# Eurorack_current_measure_PCB.net
KiCad netlist of a schematic drawn in EAGLE
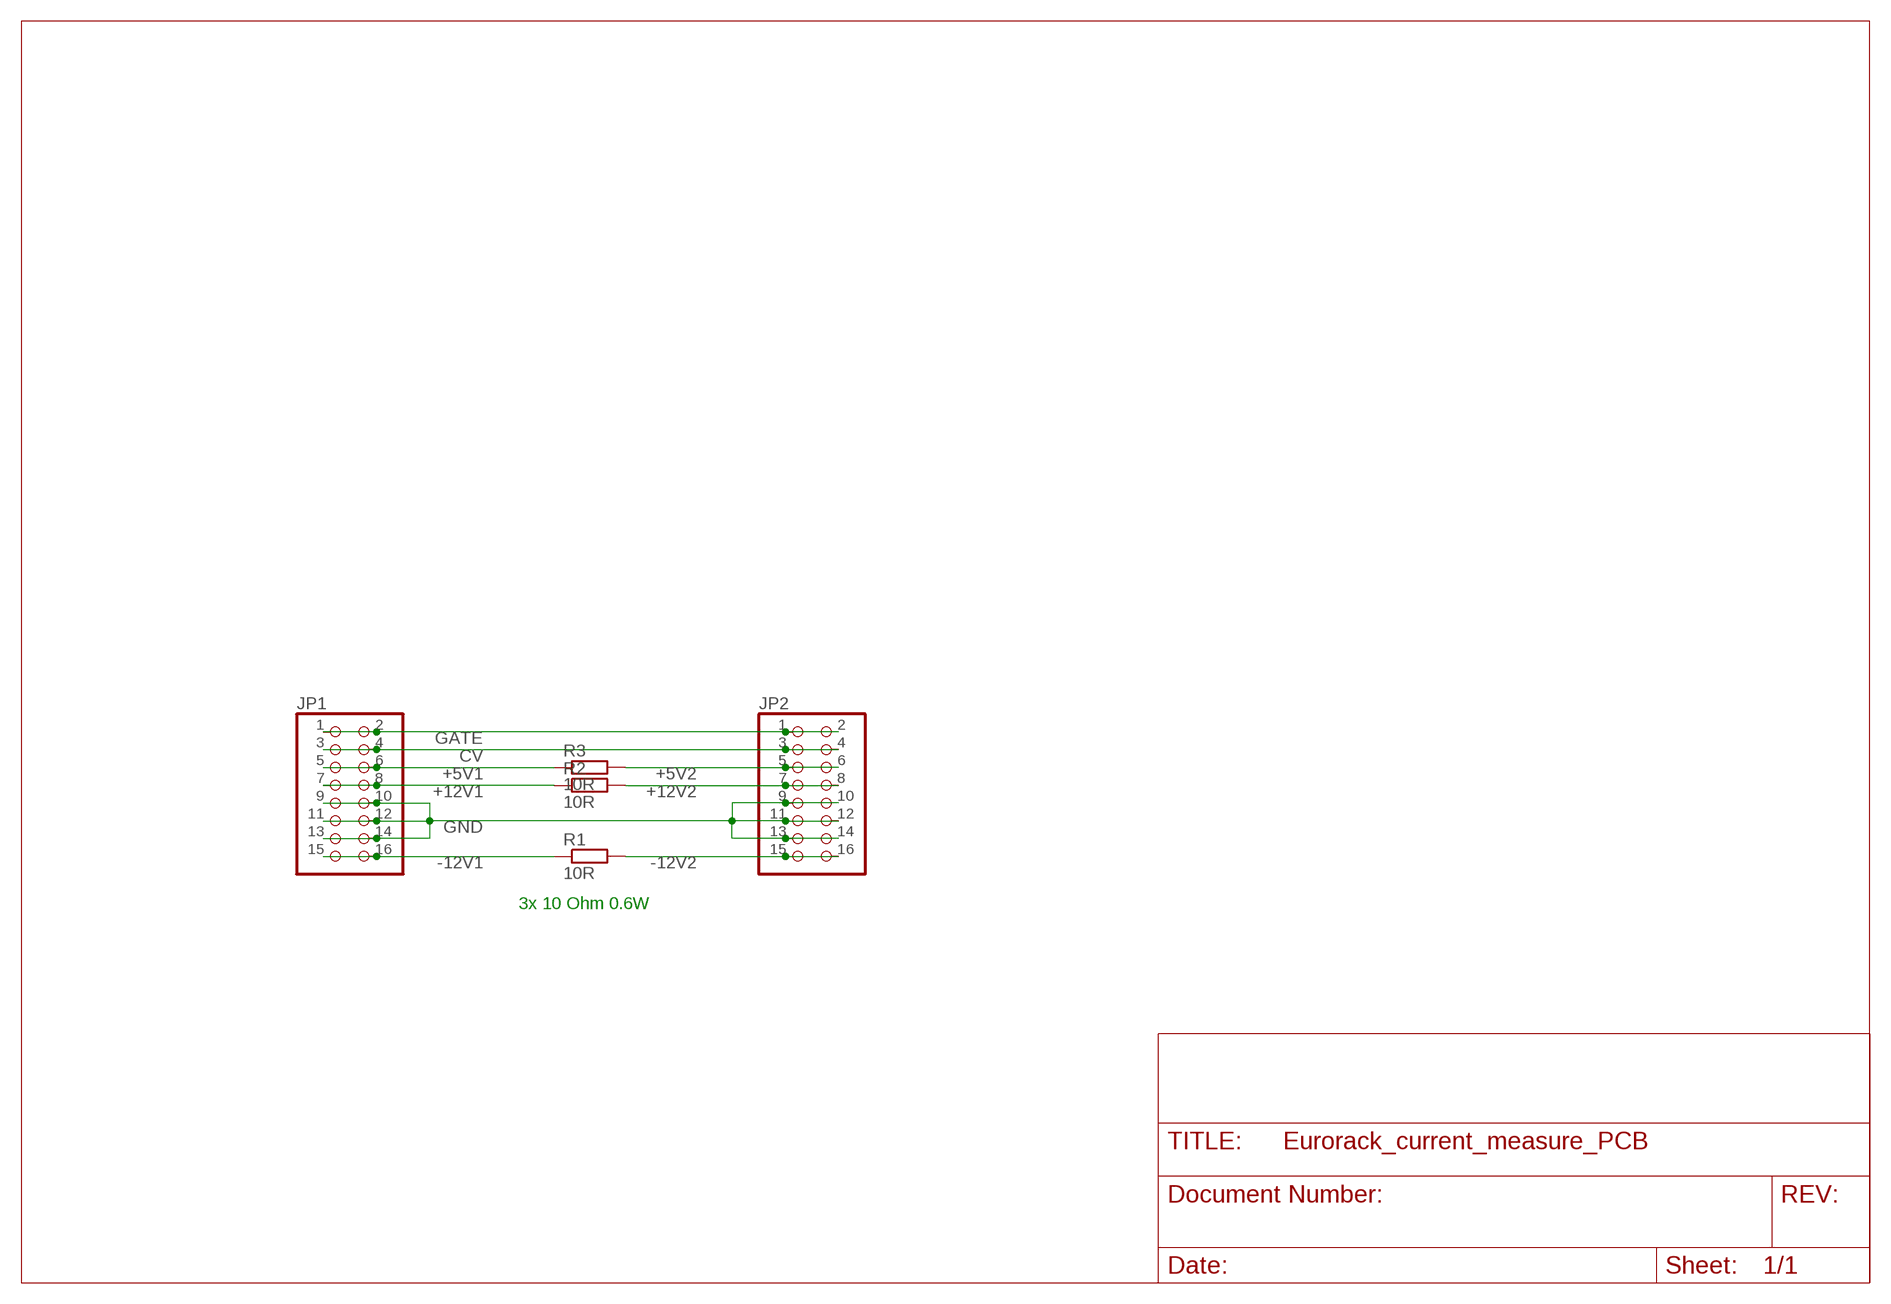
[diagram p0: schematic, sheet 1]

(export (version "E")
  (design (tool "Eeschema 10.0.6"))
  (components
    (comp (ref "JP1")
      (value "PINHD-2X8")
      (footprint "eagle-import:2X08")
      (libsource (lib "eagle-import") (part "PINHD-2X8"))
    )
    (comp (ref "JP2")
      (value "PINHD-2X8")
      (footprint "eagle-import:2X08")
      (libsource (lib "eagle-import") (part "PINHD-2X8"))
    )
    (comp (ref "R1")
      (value "10R")
      (footprint "eagle-import:0207_10")
      (libsource (lib "eagle-import") (part "R-EU_0207/10"))
    )
    (comp (ref "R2")
      (value "10R")
      (footprint "eagle-import:0207_10")
      (libsource (lib "eagle-import") (part "R-EU_0207/10"))
    )
    (comp (ref "R3")
      (value "10R")
      (footprint "eagle-import:0207_10")
      (libsource (lib "eagle-import") (part "R-EU_0207/10"))
    )
  )
  (nets
    (net (code "1") (name "/+5V1") (class "Default")
      (node (ref "JP1") (pin "5") (pinfunction "5_5") (pintype "passive"))
      (node (ref "JP1") (pin "6") (pinfunction "6_6") (pintype "passive"))
      (node (ref "R3") (pin "1") (pinfunction "1_1") (pintype "passive"))
    )
    (net (code "2") (name "/+5V2") (class "Default")
      (node (ref "JP2") (pin "5") (pinfunction "5_5") (pintype "passive"))
      (node (ref "JP2") (pin "6") (pinfunction "6_6") (pintype "passive"))
      (node (ref "R3") (pin "2") (pinfunction "2_2") (pintype "passive"))
    )
    (net (code "3") (name "/+12V1") (class "Default")
      (node (ref "JP1") (pin "7") (pinfunction "7_7") (pintype "passive"))
      (node (ref "JP1") (pin "8") (pinfunction "8_8") (pintype "passive"))
      (node (ref "R2") (pin "1") (pinfunction "1_1") (pintype "passive"))
    )
    (net (code "4") (name "/+12V2") (class "Default")
      (node (ref "JP2") (pin "7") (pinfunction "7_7") (pintype "passive"))
      (node (ref "JP2") (pin "8") (pinfunction "8_8") (pintype "passive"))
      (node (ref "R2") (pin "2") (pinfunction "2_2") (pintype "passive"))
    )
    (net (code "5") (name "/-12V1") (class "Default")
      (node (ref "JP1") (pin "15") (pinfunction "15_15") (pintype "passive"))
      (node (ref "JP1") (pin "16") (pinfunction "16_16") (pintype "passive"))
      (node (ref "R1") (pin "1") (pinfunction "1_1") (pintype "passive"))
    )
    (net (code "6") (name "/-12V2") (class "Default")
      (node (ref "JP2") (pin "15") (pinfunction "15_15") (pintype "passive"))
      (node (ref "JP2") (pin "16") (pinfunction "16_16") (pintype "passive"))
      (node (ref "R1") (pin "2") (pinfunction "2_2") (pintype "passive"))
    )
    (net (code "7") (name "/CV") (class "Default")
      (node (ref "JP1") (pin "3") (pinfunction "3_3") (pintype "passive"))
      (node (ref "JP1") (pin "4") (pinfunction "4_4") (pintype "passive"))
      (node (ref "JP2") (pin "3") (pinfunction "3_3") (pintype "passive"))
      (node (ref "JP2") (pin "4") (pinfunction "4_4") (pintype "passive"))
    )
    (net (code "8") (name "/GATE") (class "Default")
      (node (ref "JP1") (pin "1") (pinfunction "1_1") (pintype "passive"))
      (node (ref "JP1") (pin "2") (pinfunction "2_2") (pintype "passive"))
      (node (ref "JP2") (pin "1") (pinfunction "1_1") (pintype "passive"))
      (node (ref "JP2") (pin "2") (pinfunction "2_2") (pintype "passive"))
    )
    (net (code "9") (name "/GND") (class "Default")
      (node (ref "JP1") (pin "10") (pinfunction "10_10") (pintype "passive"))
      (node (ref "JP1") (pin "11") (pinfunction "11_11") (pintype "passive"))
      (node (ref "JP1") (pin "12") (pinfunction "12_12") (pintype "passive"))
      (node (ref "JP1") (pin "13") (pinfunction "13_13") (pintype "passive"))
      (node (ref "JP1") (pin "14") (pinfunction "14_14") (pintype "passive"))
      (node (ref "JP1") (pin "9") (pinfunction "9_9") (pintype "passive"))
      (node (ref "JP2") (pin "10") (pinfunction "10_10") (pintype "passive"))
      (node (ref "JP2") (pin "11") (pinfunction "11_11") (pintype "passive"))
      (node (ref "JP2") (pin "12") (pinfunction "12_12") (pintype "passive"))
      (node (ref "JP2") (pin "13") (pinfunction "13_13") (pintype "passive"))
      (node (ref "JP2") (pin "14") (pinfunction "14_14") (pintype "passive"))
      (node (ref "JP2") (pin "9") (pinfunction "9_9") (pintype "passive"))
    )
  )
)
